# motorcircuit.net
KiCad netlist of a schematic drawn in EAGLE
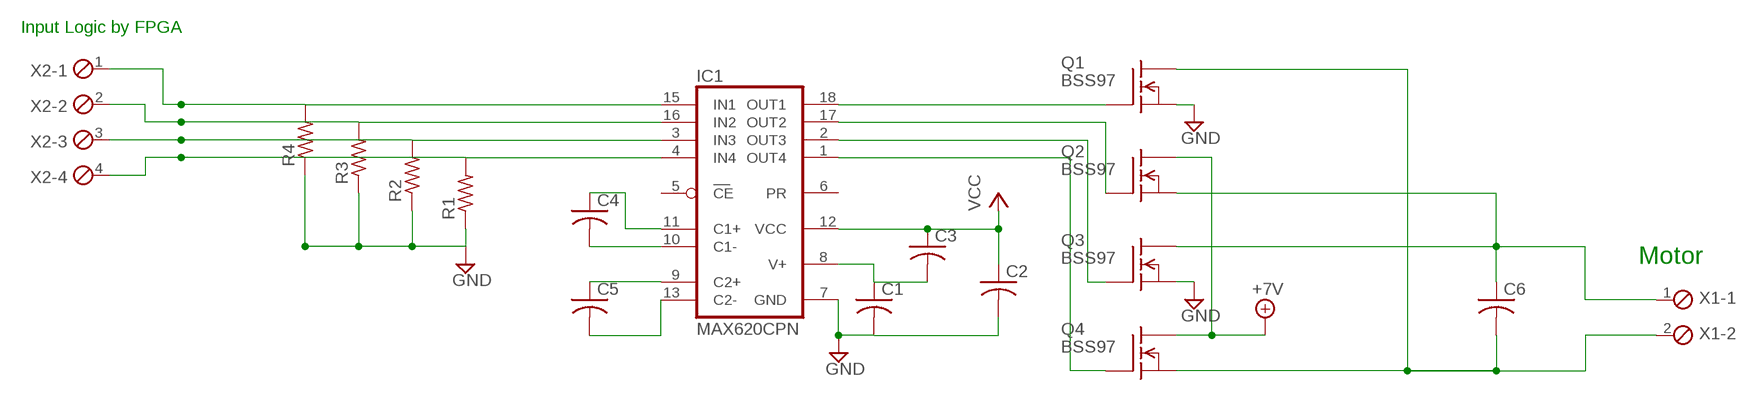
[diagram p0: schematic, sheet 1]

(export (version "E")
  (design (tool "Eeschema 10.0.6"))
  (components
    (comp (ref "C1")
      (value "C-US025-025X050")
      (footprint "eagle-import:C025-025X050")
      (libsource (lib "eagle-import") (part "C-US025-025X050"))
    )
    (comp (ref "C2")
      (value "C-US025-025X050")
      (footprint "eagle-import:C025-025X050")
      (libsource (lib "eagle-import") (part "C-US025-025X050"))
    )
    (comp (ref "C3")
      (value "C-US025-025X050")
      (footprint "eagle-import:C025-025X050")
      (libsource (lib "eagle-import") (part "C-US025-025X050"))
    )
    (comp (ref "C4")
      (value "C-US025-025X050")
      (footprint "eagle-import:C025-025X050")
      (libsource (lib "eagle-import") (part "C-US025-025X050"))
    )
    (comp (ref "C5")
      (value "C-US025-025X050")
      (footprint "eagle-import:C025-025X050")
      (libsource (lib "eagle-import") (part "C-US025-025X050"))
    )
    (comp (ref "C6")
      (value "C-US025-025X050")
      (footprint "eagle-import:C025-025X050")
      (libsource (lib "eagle-import") (part "C-US025-025X050"))
    )
    (comp (ref "IC1")
      (value "MAX620CPN")
      (footprint "eagle-import:DIL18")
      (fields (field (name "MPN") "MAX620CPN+"))
      (libsource (lib "eagle-import") (part "MAX620CPN"))
    )
    (comp (ref "Q1")
      (value "BSS97")
      (footprint "eagle-import:TO202")
      (libsource (lib "eagle-import") (part "BSS97"))
    )
    (comp (ref "Q2")
      (value "BSS97")
      (footprint "eagle-import:TO202")
      (libsource (lib "eagle-import") (part "BSS97"))
    )
    (comp (ref "Q3")
      (value "BSS97")
      (footprint "eagle-import:TO202")
      (libsource (lib "eagle-import") (part "BSS97"))
    )
    (comp (ref "Q4")
      (value "BSS97")
      (footprint "eagle-import:TO202")
      (libsource (lib "eagle-import") (part "BSS97"))
    )
    (comp (ref "R1")
      (value "R-US_0204/2V")
      (footprint "eagle-import:0204V")
      (libsource (lib "eagle-import") (part "R-US_0204/2V"))
    )
    (comp (ref "R2")
      (value "R-US_0204/2V")
      (footprint "eagle-import:0204V")
      (libsource (lib "eagle-import") (part "R-US_0204/2V"))
    )
    (comp (ref "R3")
      (value "R-US_0204/2V")
      (footprint "eagle-import:0204V")
      (libsource (lib "eagle-import") (part "R-US_0204/2V"))
    )
    (comp (ref "R4")
      (value "R-US_0204/2V")
      (footprint "eagle-import:0204V")
      (libsource (lib "eagle-import") (part "R-US_0204/2V"))
    )
    (comp (ref "X1")
      (value "MPT2")
      (footprint "eagle-import:2POL254")
      (libsource (lib "eagle-import") (part "MPT2"))
    )
    (comp (ref "X2")
      (value "MPT4")
      (footprint "eagle-import:4POL254")
      (libsource (lib "eagle-import") (part "MPT4"))
    )
  )
  (nets
    (net (code "1") (name "+7V") (class "Default")
      (node (ref "Q2") (pin "2") (pinfunction "D_2") (pintype "passive"))
      (node (ref "Q4") (pin "2") (pinfunction "D_2") (pintype "passive"))
    )
    (net (code "2") (name "GND") (class "Default")
      (node (ref "C1") (pin "2") (pinfunction "2_2") (pintype "passive"))
      (node (ref "C2") (pin "2") (pinfunction "2_2") (pintype "passive"))
      (node (ref "IC1") (pin "7") (pinfunction "GND_7") (pintype "power_in"))
      (node (ref "Q1") (pin "1") (pinfunction "S_1") (pintype "passive"))
      (node (ref "Q3") (pin "1") (pinfunction "S_1") (pintype "passive"))
      (node (ref "R1") (pin "1") (pinfunction "1_1") (pintype "passive"))
      (node (ref "R2") (pin "1") (pinfunction "1_1") (pintype "passive"))
      (node (ref "R3") (pin "1") (pinfunction "1_1") (pintype "passive"))
      (node (ref "R4") (pin "1") (pinfunction "1_1") (pintype "passive"))
    )
    (net (code "3") (name "Net-(IC1-C1+)") (class "Default")
      (node (ref "C4") (pin "1") (pinfunction "1_1") (pintype "passive"))
      (node (ref "IC1") (pin "11") (pinfunction "C1+_11") (pintype "passive"))
    )
    (net (code "4") (name "Net-(IC1-C1-)") (class "Default")
      (node (ref "C4") (pin "2") (pinfunction "2_2") (pintype "passive"))
      (node (ref "IC1") (pin "10") (pinfunction "C1-_10") (pintype "passive"))
    )
    (net (code "5") (name "Net-(IC1-C2+)") (class "Default")
      (node (ref "C5") (pin "1") (pinfunction "1_1") (pintype "passive"))
      (node (ref "IC1") (pin "9") (pinfunction "C2+_9") (pintype "passive"))
    )
    (net (code "6") (name "Net-(IC1-C2-)") (class "Default")
      (node (ref "C5") (pin "2") (pinfunction "2_2") (pintype "passive"))
      (node (ref "IC1") (pin "13") (pinfunction "C2-_13") (pintype "passive"))
    )
    (net (code "7") (name "Net-(IC1-IN1)") (class "Default")
      (node (ref "IC1") (pin "15") (pinfunction "IN1_15") (pintype "input"))
      (node (ref "R4") (pin "2") (pinfunction "2_2") (pintype "passive"))
      (node (ref "X2") (pin "1") (pinfunction "1_1") (pintype "passive"))
    )
    (net (code "8") (name "Net-(IC1-IN2)") (class "Default")
      (node (ref "IC1") (pin "16") (pinfunction "IN2_16") (pintype "input"))
      (node (ref "R3") (pin "2") (pinfunction "2_2") (pintype "passive"))
      (node (ref "X2") (pin "2") (pinfunction "1_2") (pintype "passive"))
    )
    (net (code "9") (name "Net-(IC1-IN3)") (class "Default")
      (node (ref "IC1") (pin "3") (pinfunction "IN3_3") (pintype "input"))
      (node (ref "R2") (pin "2") (pinfunction "2_2") (pintype "passive"))
      (node (ref "X2") (pin "3") (pinfunction "1_3") (pintype "passive"))
    )
    (net (code "10") (name "Net-(IC1-IN4)") (class "Default")
      (node (ref "IC1") (pin "4") (pinfunction "IN4_4") (pintype "input"))
      (node (ref "R1") (pin "2") (pinfunction "2_2") (pintype "passive"))
      (node (ref "X2") (pin "4") (pinfunction "1_4") (pintype "passive"))
    )
    (net (code "11") (name "Net-(IC1-OUT1)") (class "Default")
      (node (ref "IC1") (pin "18") (pinfunction "OUT1_18") (pintype "output"))
      (node (ref "Q1") (pin "3") (pinfunction "G_3") (pintype "passive"))
    )
    (net (code "12") (name "Net-(IC1-OUT2)") (class "Default")
      (node (ref "IC1") (pin "17") (pinfunction "OUT2_17") (pintype "output"))
      (node (ref "Q2") (pin "3") (pinfunction "G_3") (pintype "passive"))
    )
    (net (code "13") (name "Net-(IC1-OUT3)") (class "Default")
      (node (ref "IC1") (pin "2") (pinfunction "OUT3_2") (pintype "output"))
      (node (ref "Q3") (pin "3") (pinfunction "G_3") (pintype "passive"))
    )
    (net (code "14") (name "Net-(IC1-OUT4)") (class "Default")
      (node (ref "IC1") (pin "1") (pinfunction "OUT4_1") (pintype "output"))
      (node (ref "Q4") (pin "3") (pinfunction "G_3") (pintype "passive"))
    )
    (net (code "15") (name "Net-(IC1-V+)") (class "Default")
      (node (ref "C1") (pin "1") (pinfunction "1_1") (pintype "passive"))
      (node (ref "C3") (pin "2") (pinfunction "2_2") (pintype "passive"))
      (node (ref "IC1") (pin "8") (pinfunction "V+_8") (pintype "power_in"))
    )
    (net (code "16") (name "Net-(Q1-D)") (class "Default")
      (node (ref "C6") (pin "2") (pinfunction "2_2") (pintype "passive"))
      (node (ref "Q1") (pin "2") (pinfunction "D_2") (pintype "passive"))
      (node (ref "Q4") (pin "1") (pinfunction "S_1") (pintype "passive"))
      (node (ref "X1") (pin "2") (pinfunction "1_2") (pintype "passive"))
    )
    (net (code "17") (name "Net-(Q2-S)") (class "Default")
      (node (ref "C6") (pin "1") (pinfunction "1_1") (pintype "passive"))
      (node (ref "Q2") (pin "1") (pinfunction "S_1") (pintype "passive"))
      (node (ref "Q3") (pin "2") (pinfunction "D_2") (pintype "passive"))
      (node (ref "X1") (pin "1") (pinfunction "1_1") (pintype "passive"))
    )
    (net (code "18") (name "VCC") (class "Default")
      (node (ref "C2") (pin "1") (pinfunction "1_1") (pintype "passive"))
      (node (ref "C3") (pin "1") (pinfunction "1_1") (pintype "passive"))
      (node (ref "IC1") (pin "12") (pinfunction "VCC_12") (pintype "power_in"))
    )
    (net (code "19") (name "unconnected-(IC1-CE-Pad5)") (class "Default")
      (node (ref "IC1") (pin "5") (pinfunction "CE_5") (pintype "input"))
    )
    (net (code "20") (name "unconnected-(IC1-PR-Pad6)") (class "Default")
      (node (ref "IC1") (pin "6") (pinfunction "PR_6") (pintype "output"))
    )
  )
)
